# QL_keyboard.net
KiCad netlist of a schematic drawn in EAGLE
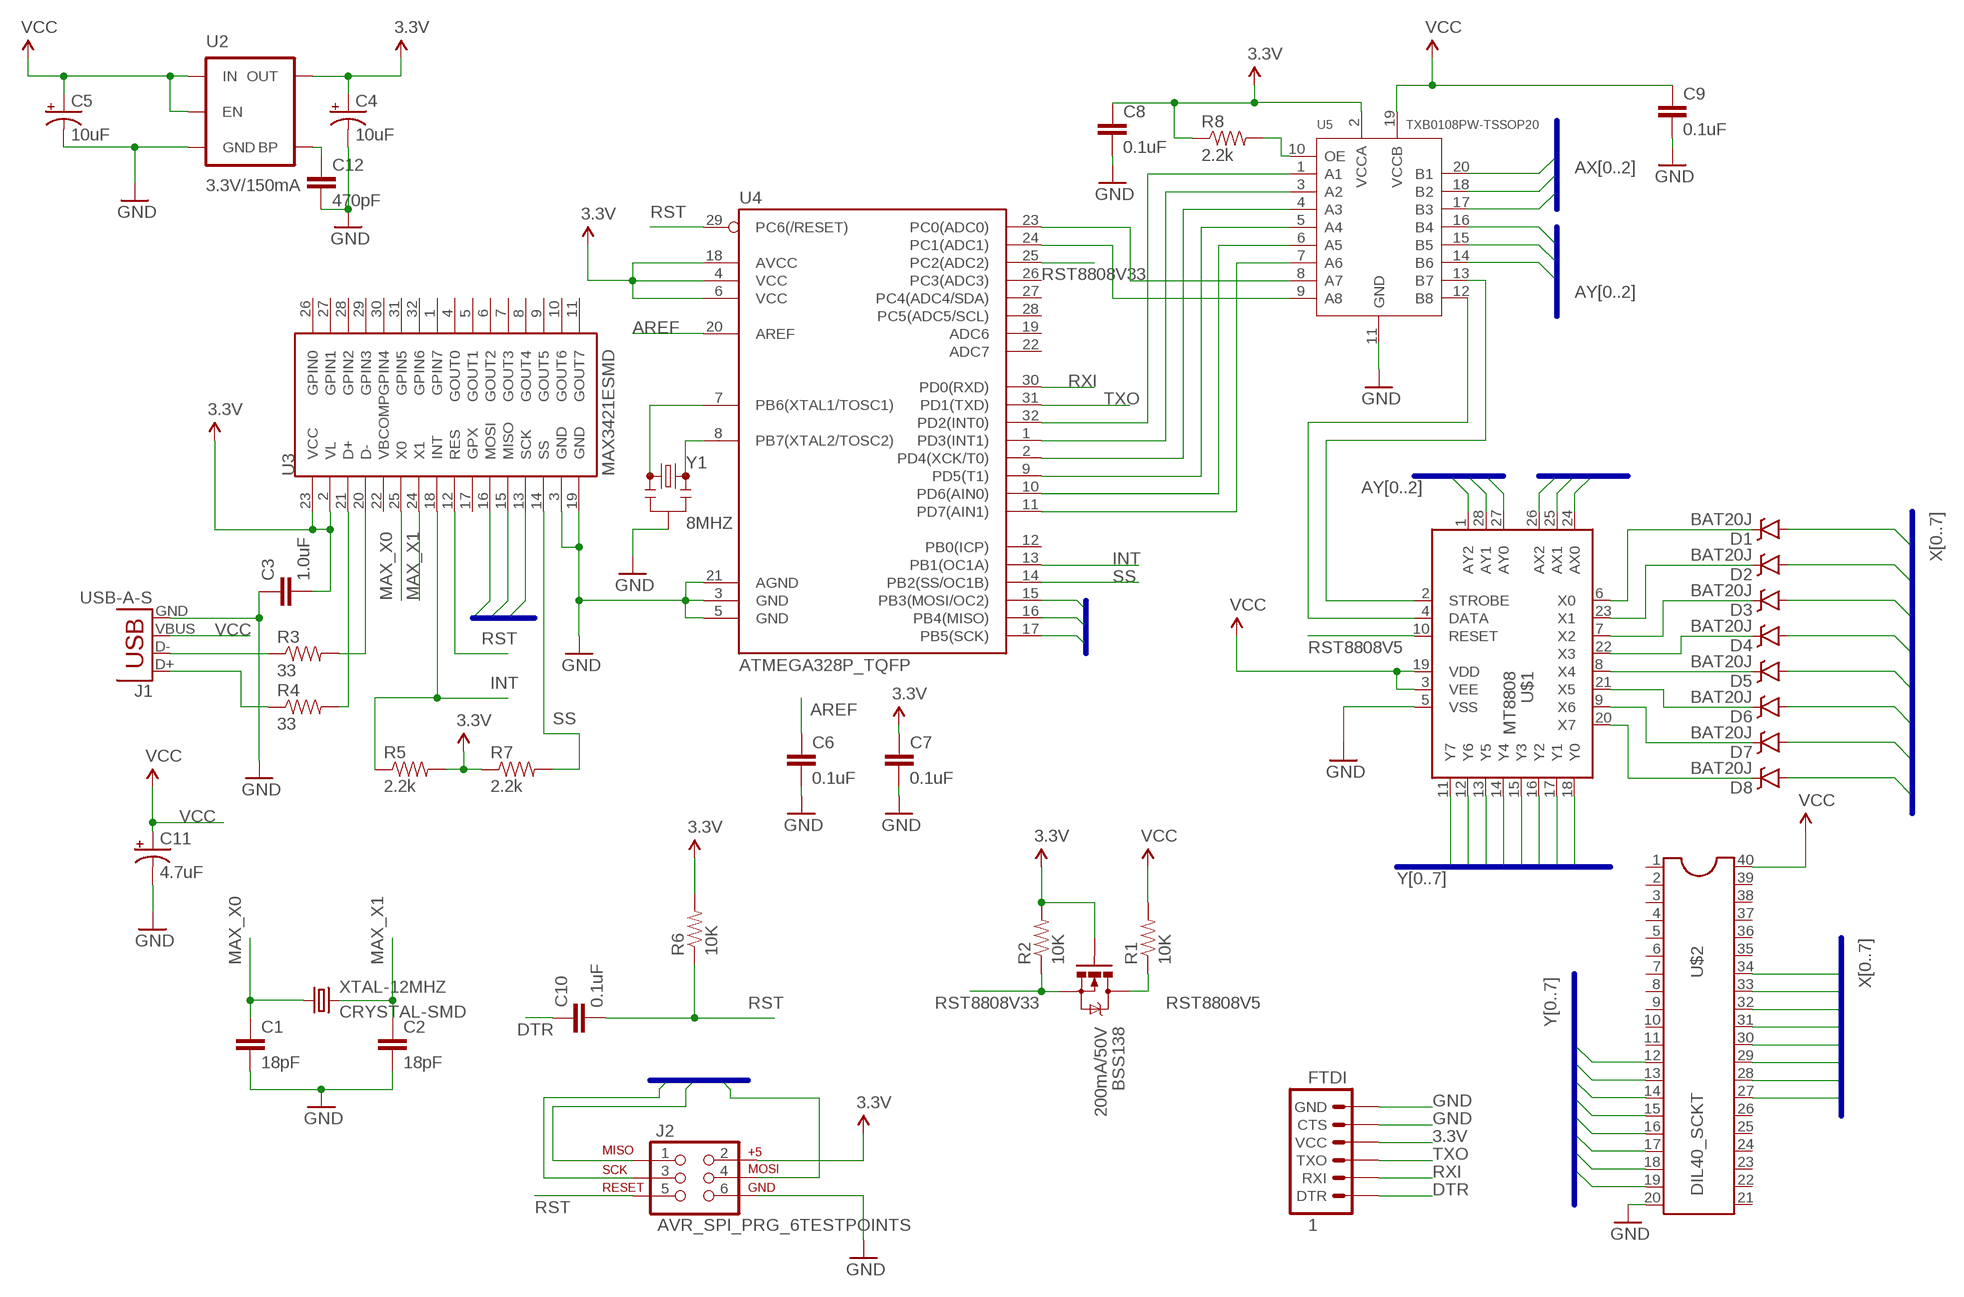
[diagram p0: schematic, sheet 1]

(export (version "E")
  (design (tool "Eeschema 10.0.6"))
  (components
    (comp (ref "BSS138")
      (value "200mA/50V")
      (footprint "eagle-import:SOT23-3")
      (libsource (lib "eagle-import") (part "MOSFET-NCHANNELBSS138"))
    )
    (comp (ref "C1")
      (value "18pF")
      (footprint "eagle-import:0603-CAP")
      (libsource (lib "eagle-import") (part "CAP0603-CAP"))
    )
    (comp (ref "C2")
      (value "18pF")
      (footprint "eagle-import:0603-CAP")
      (libsource (lib "eagle-import") (part "CAP0603-CAP"))
    )
    (comp (ref "C3")
      (value "1.0uF")
      (footprint "eagle-import:0603-CAP")
      (libsource (lib "eagle-import") (part "1.0UF-16V-10%(0603)"))
    )
    (comp (ref "C4")
      (value "10uF")
      (footprint "eagle-import:EIA3216")
      (libsource (lib "eagle-import") (part "10UF-16V-10%(TANT)"))
    )
    (comp (ref "C5")
      (value "10uF")
      (footprint "eagle-import:EIA3216")
      (libsource (lib "eagle-import") (part "10UF-16V-10%(TANT)"))
    )
    (comp (ref "C6")
      (value "0.1uF")
      (footprint "eagle-import:0603-CAP")
      (libsource (lib "eagle-import") (part "2.2UF-10V-20%(0603)"))
    )
    (comp (ref "C7")
      (value "0.1uF")
      (footprint "eagle-import:0603-CAP")
      (libsource (lib "eagle-import") (part "2.2UF-10V-20%(0603)"))
    )
    (comp (ref "C8")
      (value "0.1uF")
      (footprint "eagle-import:0603-CAP")
      (libsource (lib "eagle-import") (part "2.2UF-10V-20%(0603)"))
    )
    (comp (ref "C9")
      (value "0.1uF")
      (footprint "eagle-import:0603-CAP")
      (libsource (lib "eagle-import") (part "2.2UF-10V-20%(0603)"))
    )
    (comp (ref "C10")
      (value "0.1uF")
      (footprint "eagle-import:0603-CAP")
      (libsource (lib "eagle-import") (part "2.2UF-10V-20%(0603)"))
    )
    (comp (ref "C11")
      (value "4.7uF")
      (footprint "eagle-import:0603-POL")
      (libsource (lib "eagle-import") (part "10UF-6.3V-20%(0603)(TANT){dblquote}"))
    )
    (comp (ref "C12")
      (value "470pF")
      (footprint "eagle-import:0603-CAP")
      (libsource (lib "eagle-import") (part "2.2UF-10V-20%(0603)"))
    )
    (comp (ref "D1")
      (value "BAT20J")
      (footprint "eagle-import:SOD-323")
      (libsource (lib "eagle-import") (part "DIODE-SCHOTTKY-BAT20J"))
    )
    (comp (ref "D2")
      (value "BAT20J")
      (footprint "eagle-import:SOD-323")
      (libsource (lib "eagle-import") (part "DIODE-SCHOTTKY-BAT20J"))
    )
    (comp (ref "D3")
      (value "BAT20J")
      (footprint "eagle-import:SOD-323")
      (libsource (lib "eagle-import") (part "DIODE-SCHOTTKY-BAT20J"))
    )
    (comp (ref "D4")
      (value "BAT20J")
      (footprint "eagle-import:SOD-323")
      (libsource (lib "eagle-import") (part "DIODE-SCHOTTKY-BAT20J"))
    )
    (comp (ref "D5")
      (value "BAT20J")
      (footprint "eagle-import:SOD-323")
      (libsource (lib "eagle-import") (part "DIODE-SCHOTTKY-BAT20J"))
    )
    (comp (ref "D6")
      (value "BAT20J")
      (footprint "eagle-import:SOD-323")
      (libsource (lib "eagle-import") (part "DIODE-SCHOTTKY-BAT20J"))
    )
    (comp (ref "D7")
      (value "BAT20J")
      (footprint "eagle-import:SOD-323")
      (libsource (lib "eagle-import") (part "DIODE-SCHOTTKY-BAT20J"))
    )
    (comp (ref "D8")
      (value "BAT20J")
      (footprint "eagle-import:SOD-323")
      (libsource (lib "eagle-import") (part "DIODE-SCHOTTKY-BAT20J"))
    )
    (comp (ref "FTDI")
      (value "1")
      (footprint "eagle-import:1X06")
      (libsource (lib "eagle-import") (part "ARDUINO_SERIAL_PROGRAMPTH"))
    )
    (comp (ref "J1")
      (value "USB-A-S")
      (footprint "eagle-import:USB-A-S")
      (libsource (lib "eagle-import") (part "USB-A-S"))
    )
    (comp (ref "J2")
      (value "AVR_SPI_PRG_6TESTPOINTS")
      (footprint "eagle-import:2X3_TEST_POINTS")
      (libsource (lib "eagle-import") (part "AVR_SPI_PRG_6TESTPOINTS"))
    )
    (comp (ref "R1")
      (value "10K")
      (footprint "eagle-import:0603-RES")
      (libsource (lib "eagle-import") (part "10KOHM-1/10W-1%(0603)0603"))
    )
    (comp (ref "R2")
      (value "10K")
      (footprint "eagle-import:0603-RES")
      (libsource (lib "eagle-import") (part "10KOHM-1/10W-1%(0603)0603"))
    )
    (comp (ref "R3")
      (value "33")
      (footprint "eagle-import:0603-RES")
      (libsource (lib "eagle-import") (part "33OHM1/10W1%(0603)"))
    )
    (comp (ref "R4")
      (value "33")
      (footprint "eagle-import:0603-RES")
      (libsource (lib "eagle-import") (part "33OHM1/10W1%(0603)"))
    )
    (comp (ref "R5")
      (value "2.2k")
      (footprint "eagle-import:0603-RES")
      (libsource (lib "eagle-import") (part "2.2KOHM-1/10W-1%(0603)"))
    )
    (comp (ref "R6")
      (value "10K")
      (footprint "eagle-import:0603-RES")
      (libsource (lib "eagle-import") (part "10KOHM-1/10W-1%(0603)0603"))
    )
    (comp (ref "R7")
      (value "2.2k")
      (footprint "eagle-import:0603-RES")
      (libsource (lib "eagle-import") (part "2.2KOHM-1/10W-1%(0603)"))
    )
    (comp (ref "R8")
      (value "2.2k")
      (footprint "eagle-import:0603-RES")
      (libsource (lib "eagle-import") (part "2.2KOHM-1/10W-1%(0603)"))
    )
    (comp (ref "U$1")
      (value "MT8808")
      (footprint "eagle-import:S28")
      (libsource (lib "eagle-import") (part "MT8808"))
    )
    (comp (ref "U$2")
      (value "DIL40_SCKT")
      (footprint "eagle-import:DIL40")
      (libsource (lib "eagle-import") (part "DIL40_SCKT"))
    )
    (comp (ref "U2")
      (value "3.3V/150mA")
      (footprint "eagle-import:SOT23-5")
      (libsource (lib "eagle-import") (part "V_REG_MIC52053.3V"))
    )
    (comp (ref "U3")
      (value "MAX3421ESMD")
      (footprint "eagle-import:TQFP32-5MM")
      (libsource (lib "eagle-import") (part "MAX3421ESMD"))
    )
    (comp (ref "U4")
      (value "ATMEGA328P_TQFP")
      (footprint "eagle-import:TQFP32-08")
      (libsource (lib "eagle-import") (part "ATMEGA328P_TQFP"))
    )
    (comp (ref "U5")
      (value "TXB0108PW-TSSOP20")
      (footprint "eagle-import:TSSOP20-0.65-6.5X4.4MM")
      (fields (field (name "MPN") "TXB0108PW"))
      (libsource (lib "eagle-import") (part "LOGIC-TXB0108PW(TSSOP20)"))
    )
    (comp (ref "XTAL-12MHZ")
      (value "CRYSTAL-SMD")
      (footprint "eagle-import:CRYSTAL-SMD-5X3.2")
      (libsource (lib "eagle-import") (part "CRYSTAL-SMD"))
    )
    (comp (ref "Y1")
      (value "8MHZ")
      (footprint "eagle-import:RESONATOR-SMD")
      (libsource (lib "eagle-import") (part "RESONATOR8MHZ"))
    )
  )
  (nets
    (net (code "1") (name "/AREF") (class "Default")
      (node (ref "C6") (pin "1") (pinfunction "1_1") (pintype "passive"))
      (node (ref "U4") (pin "20") (pinfunction "AREF_20") (pintype "bidirectional"))
    )
    (net (code "2") (name "/AX0") (class "Default")
      (node (ref "U$1") (pin "24") (pinfunction "AX0_24") (pintype "input"))
      (node (ref "U5") (pin "20") (pinfunction "B1_20") (pintype "bidirectional"))
    )
    (net (code "3") (name "/AX1") (class "Default")
      (node (ref "U$1") (pin "25") (pinfunction "AX1_25") (pintype "input"))
      (node (ref "U5") (pin "18") (pinfunction "B2_18") (pintype "bidirectional"))
    )
    (net (code "4") (name "/AX2") (class "Default")
      (node (ref "U$1") (pin "26") (pinfunction "AX2_26") (pintype "input"))
      (node (ref "U5") (pin "17") (pinfunction "B3_17") (pintype "bidirectional"))
    )
    (net (code "6") (name "/AY0") (class "Default")
      (node (ref "U$1") (pin "27") (pinfunction "AY0_27") (pintype "input"))
      (node (ref "U5") (pin "16") (pinfunction "B4_16") (pintype "bidirectional"))
    )
    (net (code "7") (name "/AY1") (class "Default")
      (node (ref "U$1") (pin "28") (pinfunction "AY1_28") (pintype "input"))
      (node (ref "U5") (pin "15") (pinfunction "B5_15") (pintype "bidirectional"))
    )
    (net (code "8") (name "/AY2") (class "Default")
      (node (ref "U$1") (pin "1") (pinfunction "AY2_1") (pintype "input"))
      (node (ref "U5") (pin "14") (pinfunction "B6_14") (pintype "bidirectional"))
    )
    (net (code "10") (name "/DTR") (class "Default")
      (node (ref "C10") (pin "1") (pinfunction "1_1") (pintype "passive"))
      (node (ref "FTDI") (pin "1") (pinfunction "DTR_1") (pintype "passive"))
    )
    (net (code "11") (name "/INT") (class "Default")
      (node (ref "R5") (pin "1") (pinfunction "1_1") (pintype "passive"))
      (node (ref "U3") (pin "18") (pinfunction "INT_18") (pintype "bidirectional"))
      (node (ref "U4") (pin "13") (pinfunction "PB1(OC1A)_13") (pintype "bidirectional"))
    )
    (net (code "12") (name "/MAX_X0") (class "Default")
      (node (ref "C1") (pin "1") (pinfunction "1_1") (pintype "passive"))
      (node (ref "U3") (pin "25") (pinfunction "X0_25") (pintype "bidirectional"))
      (node (ref "XTAL-12MHZ") (pin "1") (pinfunction "1_1") (pintype "passive"))
    )
    (net (code "13") (name "/MAX_X1") (class "Default")
      (node (ref "C2") (pin "1") (pinfunction "1_1") (pintype "passive"))
      (node (ref "U3") (pin "24") (pinfunction "X1_24") (pintype "bidirectional"))
      (node (ref "XTAL-12MHZ") (pin "2") (pinfunction "2_2") (pintype "passive"))
    )
    (net (code "14") (name "/MISO") (class "Default")
      (node (ref "J2") (pin "1") (pinfunction "1_1") (pintype "passive"))
      (node (ref "U3") (pin "15") (pinfunction "MISO_15") (pintype "bidirectional"))
      (node (ref "U4") (pin "16") (pinfunction "PB4(MISO)_16") (pintype "bidirectional"))
    )
    (net (code "15") (name "/MOSI") (class "Default")
      (node (ref "J2") (pin "4") (pinfunction "4_4") (pintype "passive"))
      (node (ref "U3") (pin "16") (pinfunction "MOSI_16") (pintype "bidirectional"))
      (node (ref "U4") (pin "15") (pinfunction "PB3(MOSI/OC2)_15") (pintype "bidirectional"))
    )
    (net (code "16") (name "/RST") (class "Default")
      (node (ref "C10") (pin "2") (pinfunction "2_2") (pintype "passive"))
      (node (ref "J2") (pin "5") (pinfunction "5_5") (pintype "passive"))
      (node (ref "R6") (pin "1") (pinfunction "1_1") (pintype "passive"))
      (node (ref "U3") (pin "12") (pinfunction "RES_12") (pintype "bidirectional"))
      (node (ref "U4") (pin "29") (pinfunction "PC6(/RESET)_29") (pintype "bidirectional"))
    )
    (net (code "17") (name "/RST8808V5") (class "Default")
      (node (ref "BSS138") (pin "3") (pinfunction "D_3") (pintype "passive"))
      (node (ref "R1") (pin "1") (pinfunction "1_1") (pintype "passive"))
      (node (ref "U$1") (pin "10") (pinfunction "RESET_10") (pintype "input"))
    )
    (net (code "18") (name "/RST8808V33") (class "Default")
      (node (ref "BSS138") (pin "2") (pinfunction "S_2") (pintype "passive"))
      (node (ref "R2") (pin "1") (pinfunction "1_1") (pintype "passive"))
      (node (ref "U4") (pin "25") (pinfunction "PC2(ADC2)_25") (pintype "bidirectional"))
    )
    (net (code "19") (name "/RXI") (class "Default")
      (node (ref "FTDI") (pin "2") (pinfunction "RXI_2") (pintype "passive"))
      (node (ref "U4") (pin "30") (pinfunction "PD0(RXD)_30") (pintype "bidirectional"))
    )
    (net (code "20") (name "/SCK") (class "Default")
      (node (ref "J2") (pin "3") (pinfunction "3_3") (pintype "passive"))
      (node (ref "U3") (pin "13") (pinfunction "SCK_13") (pintype "bidirectional"))
      (node (ref "U4") (pin "17") (pinfunction "PB5(SCK)_17") (pintype "bidirectional"))
    )
    (net (code "21") (name "/SS") (class "Default")
      (node (ref "R7") (pin "2") (pinfunction "2_2") (pintype "passive"))
      (node (ref "U3") (pin "14") (pinfunction "SS_14") (pintype "bidirectional"))
      (node (ref "U4") (pin "14") (pinfunction "PB2(SS/OC1B)_14") (pintype "bidirectional"))
    )
    (net (code "22") (name "/TXO") (class "Default")
      (node (ref "FTDI") (pin "3") (pinfunction "TXO_3") (pintype "passive"))
      (node (ref "U4") (pin "31") (pinfunction "PD1(TXD)_31") (pintype "bidirectional"))
    )
    (net (code "23") (name "/X0") (class "Default")
      (node (ref "D1") (pin "A") (pinfunction "A_A") (pintype "passive"))
      (node (ref "U$2") (pin "27") (pinfunction "27_27") (pintype "passive"))
    )
    (net (code "24") (name "/X1") (class "Default")
      (node (ref "D2") (pin "A") (pinfunction "A_A") (pintype "passive"))
      (node (ref "U$2") (pin "28") (pinfunction "28_28") (pintype "passive"))
    )
    (net (code "25") (name "/X2") (class "Default")
      (node (ref "D3") (pin "A") (pinfunction "A_A") (pintype "passive"))
      (node (ref "U$2") (pin "29") (pinfunction "29_29") (pintype "passive"))
    )
    (net (code "26") (name "/X3") (class "Default")
      (node (ref "D4") (pin "A") (pinfunction "A_A") (pintype "passive"))
      (node (ref "U$2") (pin "30") (pinfunction "30_30") (pintype "passive"))
    )
    (net (code "27") (name "/X4") (class "Default")
      (node (ref "D5") (pin "A") (pinfunction "A_A") (pintype "passive"))
      (node (ref "U$2") (pin "31") (pinfunction "31_31") (pintype "passive"))
    )
    (net (code "28") (name "/X5") (class "Default")
      (node (ref "D6") (pin "A") (pinfunction "A_A") (pintype "passive"))
      (node (ref "U$2") (pin "32") (pinfunction "32_32") (pintype "passive"))
    )
    (net (code "29") (name "/X6") (class "Default")
      (node (ref "D7") (pin "A") (pinfunction "A_A") (pintype "passive"))
      (node (ref "U$2") (pin "33") (pinfunction "33_33") (pintype "passive"))
    )
    (net (code "30") (name "/X7") (class "Default")
      (node (ref "D8") (pin "A") (pinfunction "A_A") (pintype "passive"))
      (node (ref "U$2") (pin "34") (pinfunction "34_34") (pintype "passive"))
    )
    (net (code "32") (name "/Y0") (class "Default")
      (node (ref "U$1") (pin "18") (pinfunction "Y0_18") (pintype "bidirectional"))
      (node (ref "U$2") (pin "12") (pinfunction "12_12") (pintype "passive"))
    )
    (net (code "33") (name "/Y1") (class "Default")
      (node (ref "U$1") (pin "17") (pinfunction "Y1_17") (pintype "bidirectional"))
      (node (ref "U$2") (pin "13") (pinfunction "13_13") (pintype "passive"))
    )
    (net (code "34") (name "/Y2") (class "Default")
      (node (ref "U$1") (pin "16") (pinfunction "Y2_16") (pintype "bidirectional"))
      (node (ref "U$2") (pin "14") (pinfunction "14_14") (pintype "passive"))
    )
    (net (code "35") (name "/Y3") (class "Default")
      (node (ref "U$1") (pin "15") (pinfunction "Y3_15") (pintype "bidirectional"))
      (node (ref "U$2") (pin "15") (pinfunction "15_15") (pintype "passive"))
    )
    (net (code "36") (name "/Y4") (class "Default")
      (node (ref "U$1") (pin "14") (pinfunction "Y4_14") (pintype "bidirectional"))
      (node (ref "U$2") (pin "16") (pinfunction "16_16") (pintype "passive"))
    )
    (net (code "37") (name "/Y5") (class "Default")
      (node (ref "U$1") (pin "13") (pinfunction "Y5_13") (pintype "bidirectional"))
      (node (ref "U$2") (pin "17") (pinfunction "17_17") (pintype "passive"))
    )
    (net (code "38") (name "/Y6") (class "Default")
      (node (ref "U$1") (pin "12") (pinfunction "Y6_12") (pintype "bidirectional"))
      (node (ref "U$2") (pin "18") (pinfunction "18_18") (pintype "passive"))
    )
    (net (code "39") (name "/Y7") (class "Default")
      (node (ref "U$1") (pin "11") (pinfunction "Y7_11") (pintype "bidirectional"))
      (node (ref "U$2") (pin "19") (pinfunction "19_19") (pintype "passive"))
    )
    (net (code "42") (name "3.3V") (class "Default")
      (node (ref "BSS138") (pin "1") (pinfunction "G_1") (pintype "passive"))
      (node (ref "C3") (pin "2") (pinfunction "2_2") (pintype "passive"))
      (node (ref "C4") (pin "A") (pinfunction "+_A") (pintype "passive"))
      (node (ref "C7") (pin "1") (pinfunction "1_1") (pintype "passive"))
      (node (ref "C8") (pin "1") (pinfunction "1_1") (pintype "passive"))
      (node (ref "FTDI") (pin "4") (pinfunction "VCC_4") (pintype "passive"))
      (node (ref "J2") (pin "2") (pinfunction "2_2") (pintype "passive"))
      (node (ref "R2") (pin "2") (pinfunction "2_2") (pintype "passive"))
      (node (ref "R5") (pin "2") (pinfunction "2_2") (pintype "passive"))
      (node (ref "R6") (pin "2") (pinfunction "2_2") (pintype "passive"))
      (node (ref "R7") (pin "1") (pinfunction "1_1") (pintype "passive"))
      (node (ref "R8") (pin "1") (pinfunction "1_1") (pintype "passive"))
      (node (ref "U2") (pin "5") (pinfunction "OUT_5") (pintype "passive"))
      (node (ref "U3") (pin "2") (pinfunction "VL_2") (pintype "bidirectional"))
      (node (ref "U3") (pin "23") (pinfunction "VCC_23") (pintype "bidirectional"))
      (node (ref "U4") (pin "18") (pinfunction "AVCC_18") (pintype "bidirectional"))
      (node (ref "U4") (pin "4") (pinfunction "VCC_4") (pintype "bidirectional"))
      (node (ref "U4") (pin "6") (pinfunction "VCC_6") (pintype "bidirectional"))
      (node (ref "U5") (pin "2") (pinfunction "VCCA_2") (pintype "bidirectional"))
    )
    (net (code "43") (name "GND") (class "Default")
      (node (ref "C1") (pin "2") (pinfunction "2_2") (pintype "passive"))
      (node (ref "C11") (pin "K") (pinfunction "-_K") (pintype "passive"))
      (node (ref "C12") (pin "2") (pinfunction "2_2") (pintype "passive"))
      (node (ref "C2") (pin "2") (pinfunction "2_2") (pintype "passive"))
      (node (ref "C3") (pin "1") (pinfunction "1_1") (pintype "passive"))
      (node (ref "C4") (pin "C") (pinfunction "-_C") (pintype "passive"))
      (node (ref "C5") (pin "C") (pinfunction "-_C") (pintype "passive"))
      (node (ref "C6") (pin "2") (pinfunction "2_2") (pintype "passive"))
      (node (ref "C7") (pin "2") (pinfunction "2_2") (pintype "passive"))
      (node (ref "C8") (pin "2") (pinfunction "2_2") (pintype "passive"))
      (node (ref "C9") (pin "2") (pinfunction "2_2") (pintype "passive"))
      (node (ref "FTDI") (pin "5") (pinfunction "CTS_5") (pintype "passive"))
      (node (ref "FTDI") (pin "6") (pinfunction "GND_6") (pintype "passive"))
      (node (ref "J1") (pin "GND") (pinfunction "GND_GND") (pintype "bidirectional"))
      (node (ref "J2") (pin "6") (pinfunction "6_6") (pintype "passive"))
      (node (ref "U$1") (pin "5") (pinfunction "VSS_5") (pintype "power_in"))
      (node (ref "U$2") (pin "20") (pinfunction "20_20") (pintype "passive"))
      (node (ref "U2") (pin "2") (pinfunction "GND_2") (pintype "input"))
      (node (ref "U3") (pin "19") (pinfunction "GND_19") (pintype "bidirectional"))
      (node (ref "U3") (pin "3") (pinfunction "GND_3") (pintype "bidirectional"))
      (node (ref "U4") (pin "21") (pinfunction "AGND_21") (pintype "bidirectional"))
      (node (ref "U4") (pin "3") (pinfunction "GND_3") (pintype "bidirectional"))
      (node (ref "U4") (pin "5") (pinfunction "GND_5") (pintype "bidirectional"))
      (node (ref "U5") (pin "11") (pinfunction "GND_11") (pintype "bidirectional"))
      (node (ref "Y1") (pin "2") (pinfunction "2_2") (pintype "passive"))
    )
    (net (code "44") (name "Net-(J1-PadD+)") (class "Default")
      (node (ref "J1") (pin "D+") (pinfunction "D+_D+") (pintype "bidirectional"))
      (node (ref "R4") (pin "1") (pinfunction "1_1") (pintype "passive"))
    )
    (net (code "45") (name "Net-(J1-PadD-)") (class "Default")
      (node (ref "J1") (pin "D-") (pinfunction "D-_D-") (pintype "bidirectional"))
      (node (ref "R3") (pin "1") (pinfunction "1_1") (pintype "passive"))
    )
    (net (code "46") (name "Net-(U$1-DATA)") (class "Default")
      (node (ref "U$1") (pin "4") (pinfunction "DATA_4") (pintype "input"))
      (node (ref "U5") (pin "12") (pinfunction "B8_12") (pintype "bidirectional"))
    )
    (net (code "47") (name "Net-(U$1-STROBE)") (class "Default")
      (node (ref "U$1") (pin "2") (pinfunction "STROBE_2") (pintype "input"))
      (node (ref "U5") (pin "13") (pinfunction "B7_13") (pintype "bidirectional"))
    )
    (net (code "48") (name "Net-(U$1-X0)") (class "Default")
      (node (ref "D1") (pin "C") (pinfunction "C_C") (pintype "passive"))
      (node (ref "U$1") (pin "6") (pinfunction "X0_6") (pintype "bidirectional"))
    )
    (net (code "49") (name "Net-(U$1-X1)") (class "Default")
      (node (ref "D2") (pin "C") (pinfunction "C_C") (pintype "passive"))
      (node (ref "U$1") (pin "23") (pinfunction "X1_23") (pintype "bidirectional"))
    )
    (net (code "50") (name "Net-(U$1-X2)") (class "Default")
      (node (ref "D3") (pin "C") (pinfunction "C_C") (pintype "passive"))
      (node (ref "U$1") (pin "7") (pinfunction "X2_7") (pintype "bidirectional"))
    )
    (net (code "51") (name "Net-(U$1-X3)") (class "Default")
      (node (ref "D4") (pin "C") (pinfunction "C_C") (pintype "passive"))
      (node (ref "U$1") (pin "22") (pinfunction "X3_22") (pintype "bidirectional"))
    )
    (net (code "52") (name "Net-(U$1-X4)") (class "Default")
      (node (ref "D5") (pin "C") (pinfunction "C_C") (pintype "passive"))
      (node (ref "U$1") (pin "8") (pinfunction "X4_8") (pintype "bidirectional"))
    )
    (net (code "53") (name "Net-(U$1-X5)") (class "Default")
      (node (ref "D6") (pin "C") (pinfunction "C_C") (pintype "passive"))
      (node (ref "U$1") (pin "21") (pinfunction "X5_21") (pintype "bidirectional"))
    )
    (net (code "54") (name "Net-(U$1-X6)") (class "Default")
      (node (ref "D7") (pin "C") (pinfunction "C_C") (pintype "passive"))
      (node (ref "U$1") (pin "9") (pinfunction "X6_9") (pintype "bidirectional"))
    )
    (net (code "55") (name "Net-(U$1-X7)") (class "Default")
      (node (ref "D8") (pin "C") (pinfunction "C_C") (pintype "passive"))
      (node (ref "U$1") (pin "20") (pinfunction "X7_20") (pintype "bidirectional"))
    )
    (net (code "56") (name "Net-(U2-BP)") (class "Default")
      (node (ref "C12") (pin "1") (pinfunction "1_1") (pintype "passive"))
      (node (ref "U2") (pin "4") (pinfunction "BP_4") (pintype "input"))
    )
    (net (code "57") (name "Net-(U3-D+)") (class "Default")
      (node (ref "R4") (pin "2") (pinfunction "2_2") (pintype "passive"))
      (node (ref "U3") (pin "21") (pinfunction "D+_21") (pintype "bidirectional"))
    )
    (net (code "58") (name "Net-(U3-D-)") (class "Default")
      (node (ref "R3") (pin "2") (pinfunction "2_2") (pintype "passive"))
      (node (ref "U3") (pin "20") (pinfunction "D-_20") (pintype "bidirectional"))
    )
    (net (code "59") (name "Net-(U4-PB6(XTAL1{slash}TOSC1))") (class "Default")
      (node (ref "U4") (pin "7") (pinfunction "PB6(XTAL1/TOSC1)_7") (pintype "bidirectional"))
      (node (ref "Y1") (pin "1") (pinfunction "1_1") (pintype "passive"))
    )
    (net (code "60") (name "Net-(U4-PB7(XTAL2{slash}TOSC2))") (class "Default")
      (node (ref "U4") (pin "8") (pinfunction "PB7(XTAL2/TOSC2)_8") (pintype "bidirectional"))
      (node (ref "Y1") (pin "3") (pinfunction "3_3") (pintype "passive"))
    )
    (net (code "61") (name "Net-(U4-PC0(ADC0))") (class "Default")
      (node (ref "U4") (pin "23") (pinfunction "PC0(ADC0)_23") (pintype "bidirectional"))
      (node (ref "U5") (pin "8") (pinfunction "A7_8") (pintype "bidirectional"))
    )
    (net (code "62") (name "Net-(U4-PC1(ADC1))") (class "Default")
      (node (ref "U4") (pin "24") (pinfunction "PC1(ADC1)_24") (pintype "bidirectional"))
      (node (ref "U5") (pin "9") (pinfunction "A8_9") (pintype "bidirectional"))
    )
    (net (code "63") (name "Net-(U4-PD2(INT0))") (class "Default")
      (node (ref "U4") (pin "32") (pinfunction "PD2(INT0)_32") (pintype "bidirectional"))
      (node (ref "U5") (pin "1") (pinfunction "A1_1") (pintype "bidirectional"))
    )
    (net (code "64") (name "Net-(U4-PD3(INT1))") (class "Default")
      (node (ref "U4") (pin "1") (pinfunction "PD3(INT1)_1") (pintype "bidirectional"))
      (node (ref "U5") (pin "3") (pinfunction "A2_3") (pintype "bidirectional"))
    )
    (net (code "65") (name "Net-(U4-PD4(XCK{slash}T0))") (class "Default")
      (node (ref "U4") (pin "2") (pinfunction "PD4(XCK/T0)_2") (pintype "bidirectional"))
      (node (ref "U5") (pin "4") (pinfunction "A3_4") (pintype "bidirectional"))
    )
    (net (code "66") (name "Net-(U4-PD5(T1))") (class "Default")
      (node (ref "U4") (pin "9") (pinfunction "PD5(T1)_9") (pintype "bidirectional"))
      (node (ref "U5") (pin "5") (pinfunction "A4_5") (pintype "bidirectional"))
    )
    (net (code "67") (name "Net-(U4-PD6(AIN0))") (class "Default")
      (node (ref "U4") (pin "10") (pinfunction "PD6(AIN0)_10") (pintype "bidirectional"))
      (node (ref "U5") (pin "6") (pinfunction "A5_6") (pintype "bidirectional"))
    )
    (net (code "68") (name "Net-(U4-PD7(AIN1))") (class "Default")
      (node (ref "U4") (pin "11") (pinfunction "PD7(AIN1)_11") (pintype "bidirectional"))
      (node (ref "U5") (pin "7") (pinfunction "A6_7") (pintype "bidirectional"))
    )
    (net (code "69") (name "Net-(U5-OE)") (class "Default")
      (node (ref "R8") (pin "2") (pinfunction "2_2") (pintype "passive"))
      (node (ref "U5") (pin "10") (pinfunction "OE_10") (pintype "bidirectional"))
    )
    (net (code "70") (name "VCC") (class "Default")
      (node (ref "C11") (pin "A") (pinfunction "+_A") (pintype "passive"))
      (node (ref "C5") (pin "A") (pinfunction "+_A") (pintype "passive"))
      (node (ref "C9") (pin "1") (pinfunction "1_1") (pintype "passive"))
      (node (ref "J1") (pin "VBUS") (pinfunction "VBUS_VBUS") (pintype "bidirectional"))
      (node (ref "R1") (pin "2") (pinfunction "2_2") (pintype "passive"))
      (node (ref "U$1") (pin "19") (pinfunction "VDD_19") (pintype "power_in"))
      (node (ref "U$1") (pin "3") (pinfunction "VEE_3") (pintype "power_in"))
      (node (ref "U$2") (pin "40") (pinfunction "40_40") (pintype "passive"))
      (node (ref "U2") (pin "1") (pinfunction "IN_1") (pintype "input"))
      (node (ref "U2") (pin "3") (pinfunction "EN_3") (pintype "input"))
      (node (ref "U5") (pin "19") (pinfunction "VCCB_19") (pintype "bidirectional"))
    )
    (net (code "71") (name "unconnected-(U$2-Pad1)") (class "Default")
      (node (ref "U$2") (pin "1") (pinfunction "1_1") (pintype "passive"))
    )
    (net (code "72") (name "unconnected-(U$2-Pad2)") (class "Default")
      (node (ref "U$2") (pin "2") (pinfunction "2_2") (pintype "passive"))
    )
    (net (code "73") (name "unconnected-(U$2-Pad3)") (class "Default")
      (node (ref "U$2") (pin "3") (pinfunction "3_3") (pintype "passive"))
    )
    (net (code "74") (name "unconnected-(U$2-Pad4)") (class "Default")
      (node (ref "U$2") (pin "4") (pinfunction "4_4") (pintype "passive"))
    )
    (net (code "75") (name "unconnected-(U$2-Pad5)") (class "Default")
      (node (ref "U$2") (pin "5") (pinfunction "5_5") (pintype "passive"))
    )
    (net (code "76") (name "unconnected-(U$2-Pad6)") (class "Default")
      (node (ref "U$2") (pin "6") (pinfunction "6_6") (pintype "passive"))
    )
    (net (code "77") (name "unconnected-(U$2-Pad7)") (class "Default")
      (node (ref "U$2") (pin "7") (pinfunction "7_7") (pintype "passive"))
    )
    (net (code "78") (name "unconnected-(U$2-Pad8)") (class "Default")
      (node (ref "U$2") (pin "8") (pinfunction "8_8") (pintype "passive"))
    )
    (net (code "79") (name "unconnected-(U$2-Pad9)") (class "Default")
      (node (ref "U$2") (pin "9") (pinfunction "9_9") (pintype "passive"))
    )
    (net (code "80") (name "unconnected-(U$2-Pad10)") (class "Default")
      (node (ref "U$2") (pin "10") (pinfunction "10_10") (pintype "passive"))
    )
    (net (code "81") (name "unconnected-(U$2-Pad11)") (class "Default")
      (node (ref "U$2") (pin "11") (pinfunction "11_11") (pintype "passive"))
    )
    (net (code "82") (name "unconnected-(U$2-Pad21)") (class "Default")
      (node (ref "U$2") (pin "21") (pinfunction "21_21") (pintype "passive"))
    )
    (net (code "83") (name "unconnected-(U$2-Pad22)") (class "Default")
      (node (ref "U$2") (pin "22") (pinfunction "22_22") (pintype "passive"))
    )
    (net (code "84") (name "unconnected-(U$2-Pad23)") (class "Default")
      (node (ref "U$2") (pin "23") (pinfunction "23_23") (pintype "passive"))
    )
    (net (code "85") (name "unconnected-(U$2-Pad24)") (class "Default")
      (node (ref "U$2") (pin "24") (pinfunction "24_24") (pintype "passive"))
    )
    (net (code "86") (name "unconnected-(U$2-Pad25)") (class "Default")
      (node (ref "U$2") (pin "25") (pinfunction "25_25") (pintype "passive"))
    )
    (net (code "87") (name "unconnected-(U$2-Pad26)") (class "Default")
      (node (ref "U$2") (pin "26") (pinfunction "26_26") (pintype "passive"))
    )
    (net (code "88") (name "unconnected-(U$2-Pad35)") (class "Default")
      (node (ref "U$2") (pin "35") (pinfunction "35_35") (pintype "passive"))
    )
    (net (code "89") (name "unconnected-(U$2-Pad36)") (class "Default")
      (node (ref "U$2") (pin "36") (pinfunction "36_36") (pintype "passive"))
    )
    (net (code "90") (name "unconnected-(U$2-Pad37)") (class "Default")
      (node (ref "U$2") (pin "37") (pinfunction "37_37") (pintype "passive"))
    )
    (net (code "91") (name "unconnected-(U$2-Pad38)") (class "Default")
      (node (ref "U$2") (pin "38") (pinfunction "38_38") (pintype "passive"))
    )
    (net (code "92") (name "unconnected-(U$2-Pad39)") (class "Default")
      (node (ref "U$2") (pin "39") (pinfunction "39_39") (pintype "passive"))
    )
    (net (code "93") (name "unconnected-(U3-GOUT0-Pad4)") (class "Default")
      (node (ref "U3") (pin "4") (pinfunction "GOUT0_4") (pintype "bidirectional"))
    )
    (net (code "94") (name "unconnected-(U3-GOUT1-Pad5)") (class "Default")
      (node (ref "U3") (pin "5") (pinfunction "GOUT1_5") (pintype "bidirectional"))
    )
    (net (code "95") (name "unconnected-(U3-GOUT2-Pad6)") (class "Default")
      (node (ref "U3") (pin "6") (pinfunction "GOUT2_6") (pintype "bidirectional"))
    )
    (net (code "96") (name "unconnected-(U3-GOUT3-Pad7)") (class "Default")
      (node (ref "U3") (pin "7") (pinfunction "GOUT3_7") (pintype "bidirectional"))
    )
    (net (code "97") (name "unconnected-(U3-GOUT4-Pad8)") (class "Default")
      (node (ref "U3") (pin "8") (pinfunction "GOUT4_8") (pintype "bidirectional"))
    )
    (net (code "98") (name "unconnected-(U3-GOUT5-Pad9)") (class "Default")
      (node (ref "U3") (pin "9") (pinfunction "GOUT5_9") (pintype "bidirectional"))
    )
    (net (code "99") (name "unconnected-(U3-GOUT6-Pad10)") (class "Default")
      (node (ref "U3") (pin "10") (pinfunction "GOUT6_10") (pintype "bidirectional"))
    )
    (net (code "100") (name "unconnected-(U3-GOUT7-Pad11)") (class "Default")
      (node (ref "U3") (pin "11") (pinfunction "GOUT7_11") (pintype "bidirectional"))
    )
    (net (code "101") (name "unconnected-(U3-GPIN0-Pad26)") (class "Default")
      (node (ref "U3") (pin "26") (pinfunction "GPIN0_26") (pintype "bidirectional"))
    )
    (net (code "102") (name "unconnected-(U3-GPIN1-Pad27)") (class "Default")
      (node (ref "U3") (pin "27") (pinfunction "GPIN1_27") (pintype "bidirectional"))
    )
    (net (code "103") (name "unconnected-(U3-GPIN2-Pad28)") (class "Default")
      (node (ref "U3") (pin "28") (pinfunction "GPIN2_28") (pintype "bidirectional"))
    )
    (net (code "104") (name "unconnected-(U3-GPIN3-Pad29)") (class "Default")
      (node (ref "U3") (pin "29") (pinfunction "GPIN3_29") (pintype "bidirectional"))
    )
    (net (code "105") (name "unconnected-(U3-GPIN4-Pad30)") (class "Default")
      (node (ref "U3") (pin "30") (pinfunction "GPIN4_30") (pintype "bidirectional"))
    )
    (net (code "106") (name "unconnected-(U3-GPIN5-Pad31)") (class "Default")
      (node (ref "U3") (pin "31") (pinfunction "GPIN5_31") (pintype "bidirectional"))
    )
    (net (code "107") (name "unconnected-(U3-GPIN6-Pad32)") (class "Default")
      (node (ref "U3") (pin "32") (pinfunction "GPIN6_32") (pintype "bidirectional"))
    )
    (net (code "108") (name "unconnected-(U3-GPIN7-Pad1)") (class "Default")
      (node (ref "U3") (pin "1") (pinfunction "GPIN7_1") (pintype "bidirectional"))
    )
    (net (code "109") (name "unconnected-(U3-GPX-Pad17)") (class "Default")
      (node (ref "U3") (pin "17") (pinfunction "GPX_17") (pintype "bidirectional"))
    )
    (net (code "110") (name "unconnected-(U3-VBCOMP-Pad22)") (class "Default")
      (node (ref "U3") (pin "22") (pinfunction "VBCOMP_22") (pintype "bidirectional"))
    )
    (net (code "111") (name "unconnected-(U4-ADC6-Pad19)") (class "Default")
      (node (ref "U4") (pin "19") (pinfunction "ADC6_19") (pintype "bidirectional"))
    )
    (net (code "112") (name "unconnected-(U4-ADC7-Pad22)") (class "Default")
      (node (ref "U4") (pin "22") (pinfunction "ADC7_22") (pintype "bidirectional"))
    )
    (net (code "113") (name "unconnected-(U4-PB0(ICP)-Pad12)") (class "Default")
      (node (ref "U4") (pin "12") (pinfunction "PB0(ICP)_12") (pintype "bidirectional"))
    )
    (net (code "114") (name "unconnected-(U4-PC3(ADC3)-Pad26)") (class "Default")
      (node (ref "U4") (pin "26") (pinfunction "PC3(ADC3)_26") (pintype "bidirectional"))
    )
    (net (code "115") (name "unconnected-(U4-PC4(ADC4{slash}SDA)-Pad27)") (class "Default")
      (node (ref "U4") (pin "27") (pinfunction "PC4(ADC4/SDA)_27") (pintype "bidirectional"))
    )
    (net (code "116") (name "unconnected-(U4-PC5(ADC5{slash}SCL)-Pad28)") (class "Default")
      (node (ref "U4") (pin "28") (pinfunction "PC5(ADC5/SCL)_28") (pintype "bidirectional"))
    )
  )
)
